# flasher.net
KiCad netlist of a schematic drawn in EAGLE
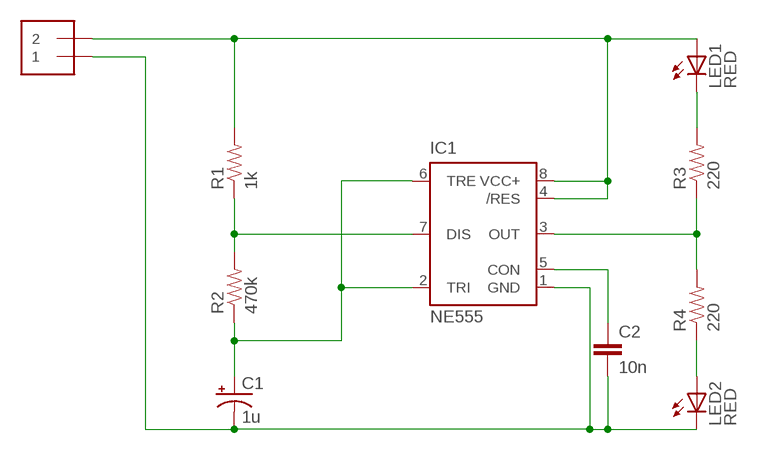
[diagram p0: schematic, sheet 1]

(export (version "E")
  (design (tool "Eeschema 10.0.6"))
  (components
    (comp (ref "C1")
      (value "1u")
      (footprint "eagle-import:CPOL-RADIAL-10UF-25V")
      (libsource (lib "eagle-import") (part "CAP_POLPTH2"))
    )
    (comp (ref "C2")
      (value "10n")
      (footprint "eagle-import:CAP-PTH-SMALL")
      (libsource (lib "eagle-import") (part "CAPPTH"))
    )
    (comp (ref "IC1")
      (value "NE555")
      (footprint "eagle-import:DIL-08")
      (fields (field (name "MF") "Arrow Electronics") (field (name "MPN") "NE555N"))
      (libsource (lib "eagle-import") (part "NE555"))
    )
    (comp (ref "J1")
      (value "1X2-3.5MM")
      (footprint "eagle-import:1X2-3.5MM")
      (libsource (lib "eagle-import") (part "1X2-3.5MM"))
    )
    (comp (ref "LED1")
      (value "RED")
      (footprint "eagle-import:LED5MM")
      (libsource (lib "eagle-import") (part "LED5MM"))
    )
    (comp (ref "LED2")
      (value "RED")
      (footprint "eagle-import:LED5MM")
      (libsource (lib "eagle-import") (part "LED5MM"))
    )
    (comp (ref "R1")
      (value "1k")
      (footprint "eagle-import:AXIAL-0.3")
      (libsource (lib "eagle-import") (part "RESISTORAXIAL-0.3"))
    )
    (comp (ref "R2")
      (value "470k")
      (footprint "eagle-import:AXIAL-0.3")
      (libsource (lib "eagle-import") (part "RESISTORAXIAL-0.3"))
    )
    (comp (ref "R3")
      (value "220")
      (footprint "eagle-import:AXIAL-0.3")
      (libsource (lib "eagle-import") (part "RESISTORAXIAL-0.3"))
    )
    (comp (ref "R4")
      (value "220")
      (footprint "eagle-import:AXIAL-0.3")
      (libsource (lib "eagle-import") (part "RESISTORAXIAL-0.3"))
    )
  )
  (nets
    (net (code "1") (name "Net-(C1-+)") (class "Default")
      (node (ref "C1") (pin "1") (pinfunction "+_1") (pintype "passive"))
      (node (ref "IC1") (pin "2") (pinfunction "TRI_2") (pintype "input"))
      (node (ref "IC1") (pin "6") (pinfunction "TRE_6") (pintype "input"))
      (node (ref "R2") (pin "P$1") (pinfunction "1_P$1") (pintype "passive"))
    )
    (net (code "2") (name "Net-(C1--)") (class "Default")
      (node (ref "C1") (pin "2") (pinfunction "-_2") (pintype "passive"))
      (node (ref "C2") (pin "2") (pinfunction "2_2") (pintype "passive"))
      (node (ref "IC1") (pin "1") (pinfunction "GND_1") (pintype "power_in"))
      (node (ref "J1") (pin "1") (pinfunction "1_1") (pintype "passive"))
      (node (ref "LED2") (pin "K") (pinfunction "C_K") (pintype "passive"))
    )
    (net (code "3") (name "Net-(IC1-CON)") (class "Default")
      (node (ref "C2") (pin "1") (pinfunction "1_1") (pintype "passive"))
      (node (ref "IC1") (pin "5") (pinfunction "CON_5") (pintype "input"))
    )
    (net (code "4") (name "Net-(IC1-DIS)") (class "Default")
      (node (ref "IC1") (pin "7") (pinfunction "DIS_7") (pintype "input"))
      (node (ref "R1") (pin "P$1") (pinfunction "1_P$1") (pintype "passive"))
      (node (ref "R2") (pin "P$2") (pinfunction "2_P$2") (pintype "passive"))
    )
    (net (code "5") (name "Net-(IC1-OUT)") (class "Default")
      (node (ref "IC1") (pin "3") (pinfunction "OUT_3") (pintype "output"))
      (node (ref "R3") (pin "P$1") (pinfunction "1_P$1") (pintype "passive"))
      (node (ref "R4") (pin "P$2") (pinfunction "2_P$2") (pintype "passive"))
    )
    (net (code "6") (name "Net-(IC1-VCC+)") (class "Default")
      (node (ref "IC1") (pin "4") (pinfunction "/RES_4") (pintype "input"))
      (node (ref "IC1") (pin "8") (pinfunction "VCC+_8") (pintype "power_in"))
      (node (ref "J1") (pin "2") (pinfunction "2_2") (pintype "passive"))
      (node (ref "LED1") (pin "A") (pinfunction "A_A") (pintype "passive"))
      (node (ref "R1") (pin "P$2") (pinfunction "2_P$2") (pintype "passive"))
    )
    (net (code "7") (name "Net-(LED1-C)") (class "Default")
      (node (ref "LED1") (pin "K") (pinfunction "C_K") (pintype "passive"))
      (node (ref "R3") (pin "P$2") (pinfunction "2_P$2") (pintype "passive"))
    )
    (net (code "8") (name "Net-(R4-1)") (class "Default")
      (node (ref "LED2") (pin "A") (pinfunction "A_A") (pintype "passive"))
      (node (ref "R4") (pin "P$1") (pinfunction "1_P$1") (pintype "passive"))
    )
  )
)
